# FET_Driver.net
KiCad netlist of a schematic drawn in Altium Designer
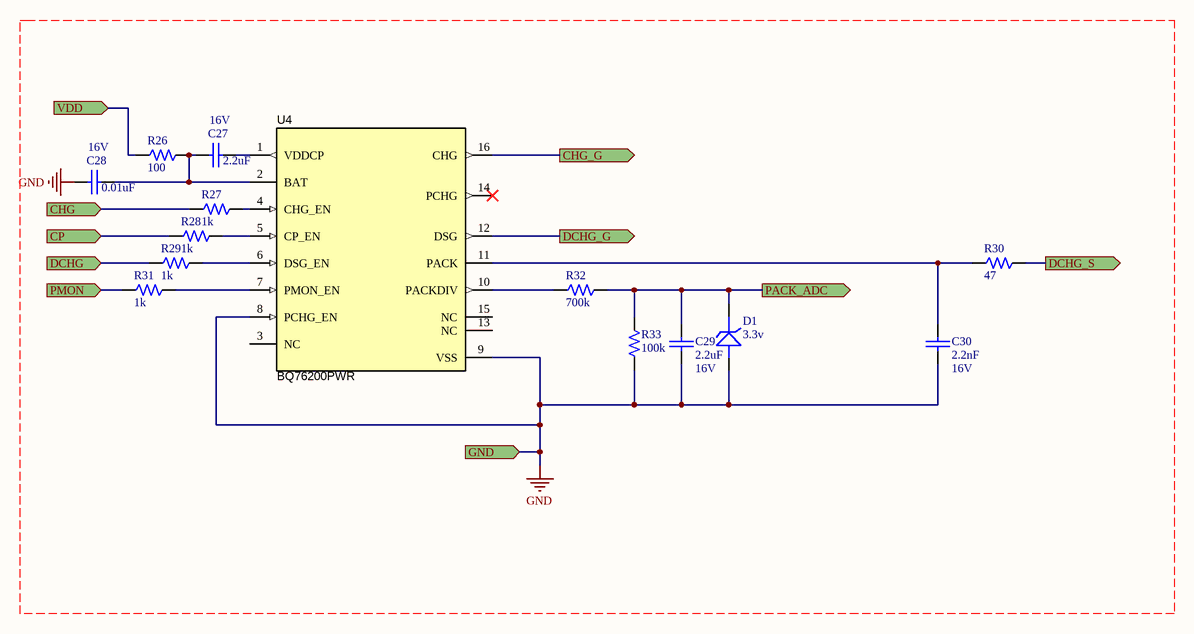
[diagram p0: FET Driver.SchDoc]

(export (version "E")
  (design (tool "Eeschema 10.0.6"))
  (components
    (comp (ref "C27")
      (value "2.2uF")
      (footprint "CAPC0603-RW")
      (description "CAP X7R .01UF 16V +-10% 0603 WALSIN L")
      (fields
        (field (name "MFG") "WALSIN")
        (field (name "TOLERANCE") "10%")
        (field (name "VOLTAGE") "16V")
        (field (name "CREATE_NAME") "Nathan")
      )
      (libsource (lib "P-Capacitors") (part "CAP0603 0.01uF 16V 10%_X7R_WALSIN"))
    )
    (comp (ref "C28")
      (value "0.01uF")
      (footprint "CAPC0603-RW")
      (description "CAP X7R .01UF 16V +-10% 0603 WALSIN L")
      (fields
        (field (name "MFG") "WALSIN")
        (field (name "TOLERANCE") "10%")
        (field (name "VOLTAGE") "16V")
        (field (name "CREATE_NAME") "Nathan")
      )
      (libsource (lib "P-Capacitors") (part "CAP0603 0.01uF 16V 10%_X7R_WALSIN"))
    )
    (comp (ref "C29")
      (value "2.2uF")
      (footprint "CAPC0603-RW")
      (description "CAP X7R .01UF 16V +-10% 0603 WALSIN L")
      (fields
        (field (name "MFG") "WALSIN")
        (field (name "TOLERANCE") "10%")
        (field (name "VOLTAGE") "16V")
        (field (name "CREATE_NAME") "Nathan")
      )
      (libsource (lib "P-Capacitors") (part "CAP0603 0.01uF 16V 10%_X7R_WALSIN"))
    )
    (comp (ref "C30")
      (value "2.2nF")
      (footprint "CAPC0603-RW")
      (description "CAP X7R .01UF 16V +-10% 0603 WALSIN L")
      (fields
        (field (name "MFG") "WALSIN")
        (field (name "TOLERANCE") "10%")
        (field (name "VOLTAGE") "16V")
        (field (name "CREATE_NAME") "Nathan")
      )
      (libsource (lib "P-Capacitors") (part "CAP0603 0.01uF 16V 10%_X7R_WALSIN"))
    )
    (comp (ref "D1")
      (value "T573004282016")
      (footprint "1206-RW")
      (description "ZD 16V 500MW 5% LL34 PAN J K")
      (fields
        (field (name "MFG") "PAN JIT")
        (field (name "POWER") "500MW")
        (field (name "MFG PART") "3.3v")
        (field (name "CREATE_NAME") "Nathan")
      )
      (libsource (lib "R-Semiconductors") (part "ZMM55-C16"))
    )
    (comp (ref "R26")
      (value "100")
      (footprint "0603-RW")
      (description "CHIP 976 OHM 100PPM +-1% 0603 WALS L")
      (fields (field (name "POWER") "0.1W") (field (name "MFG") "WALSIN") (field (name "CREATE_NAME") "Tom"))
      (libsource (lib "Q-Resistors") (part "RES0603 1/10W +-1% 976 OHM 100PPM"))
    )
    (comp (ref "R27")
      (value "1k")
      (footprint "0603-RW")
      (description "CHIP 976 OHM 100PPM +-1% 0603 WALS L")
      (fields (field (name "POWER") "0.1W") (field (name "MFG") "WALSIN") (field (name "CREATE_NAME") "Tom"))
      (libsource (lib "Q-Resistors") (part "RES0603 1/10W +-1% 976 OHM 100PPM"))
    )
    (comp (ref "R28")
      (value "1k")
      (footprint "0603-RW")
      (description "CHIP 976 OHM 100PPM +-1% 0603 WALS L")
      (fields (field (name "POWER") "0.1W") (field (name "MFG") "WALSIN") (field (name "CREATE_NAME") "Tom"))
      (libsource (lib "Q-Resistors") (part "RES0603 1/10W +-1% 976 OHM 100PPM"))
    )
    (comp (ref "R29")
      (value "1k")
      (footprint "0603-RW")
      (description "CHIP 976 OHM 100PPM +-1% 0603 WALS L")
      (fields (field (name "POWER") "0.1W") (field (name "MFG") "WALSIN") (field (name "CREATE_NAME") "Tom"))
      (libsource (lib "Q-Resistors") (part "RES0603 1/10W +-1% 976 OHM 100PPM"))
    )
    (comp (ref "R30")
      (value "47")
      (footprint "0603-RW")
      (description "CHIP 976 OHM 100PPM +-1% 0603 WALS L")
      (fields (field (name "POWER") "0.1W") (field (name "MFG") "WALSIN") (field (name "CREATE_NAME") "Tom"))
      (libsource (lib "Q-Resistors") (part "RES0603 1/10W +-1% 976 OHM 100PPM"))
    )
    (comp (ref "R31")
      (value "1k")
      (footprint "0603-RW")
      (description "CHIP 976 OHM 100PPM +-1% 0603 WALS L")
      (fields (field (name "POWER") "0.1W") (field (name "MFG") "WALSIN") (field (name "CREATE_NAME") "Tom"))
      (libsource (lib "Q-Resistors") (part "RES0603 1/10W +-1% 976 OHM 100PPM"))
    )
    (comp (ref "R32")
      (value "700k")
      (footprint "0603-RW")
      (description "CHIP 976 OHM 100PPM +-1% 0603 WALS L")
      (fields (field (name "POWER") "0.1W") (field (name "MFG") "WALSIN") (field (name "CREATE_NAME") "Tom"))
      (libsource (lib "Q-Resistors") (part "RES0603 1/10W +-1% 976 OHM 100PPM"))
    )
    (comp (ref "R33")
      (value "100k")
      (footprint "0603-RW")
      (description "CHIP 976 OHM 100PPM +-1% 0603 WALS L")
      (fields (field (name "POWER") "0.1W") (field (name "MFG") "WALSIN") (field (name "CREATE_NAME") "Tom"))
      (libsource (lib "Q-Resistors") (part "RES0603 1/10W +-1% 976 OHM 100PPM"))
    )
    (comp (ref "U4")
      (value "BQ76200PWR")
      (footprint "TSSOP16")
      (description "High-Side N-Channel FET Driver, PW0016A (TSSOP-16)")
      (fields
        (field (name "PARTNUMBER") "BQ76200PWR")
        (field (name "MANUFACTURER") "Texas Instruments")
        (field (name "ALTERNATE PARTNUMBER") "BQ76200PW")
        (field (name "PUBLISHER") "Texas Instruments")
      )
      (libsource (lib "R-Semiconductors") (part "BQ76200"))
    )
  )
  (nets
    (net (code "1") (name "/CHG") (class "Default")
      (node (ref "R27") (pin "1") (pinfunction "1_1") (pintype "passive"))
    )
    (net (code "2") (name "/CHG_G") (class "Default")
      (node (ref "U4") (pin "16") (pinfunction "CHG_16") (pintype "output"))
    )
    (net (code "3") (name "/CP") (class "Default")
      (node (ref "R28") (pin "1") (pinfunction "1_1") (pintype "passive"))
    )
    (net (code "4") (name "/DCHG") (class "Default")
      (node (ref "R29") (pin "1") (pinfunction "1_1") (pintype "passive"))
    )
    (net (code "5") (name "/DCHG_G") (class "Default")
      (node (ref "U4") (pin "12") (pinfunction "DSG_12") (pintype "output"))
    )
    (net (code "6") (name "/DCHG_S") (class "Default")
      (node (ref "R30") (pin "2") (pinfunction "2_2") (pintype "passive"))
    )
    (net (code "7") (name "/PACK_ADC") (class "Default")
      (node (ref "C29") (pin "2") (pinfunction "2_2") (pintype "passive"))
      (node (ref "D1") (pin "2") (pinfunction "K_2") (pintype "passive"))
      (node (ref "R32") (pin "2") (pinfunction "2_2") (pintype "passive"))
      (node (ref "R33") (pin "2") (pinfunction "2_2") (pintype "passive"))
    )
    (net (code "8") (name "/PMON") (class "Default")
      (node (ref "R31") (pin "1") (pinfunction "1_1") (pintype "passive"))
    )
    (net (code "9") (name "/VDD") (class "Default")
      (node (ref "R26") (pin "1") (pinfunction "1_1") (pintype "passive"))
    )
    (net (code "10") (name "GND") (class "Default")
      (node (ref "C28") (pin "1") (pinfunction "1_1") (pintype "passive"))
      (node (ref "C29") (pin "1") (pinfunction "1_1") (pintype "passive"))
      (node (ref "C30") (pin "1") (pinfunction "1_1") (pintype "passive"))
      (node (ref "D1") (pin "1") (pinfunction "A_1") (pintype "passive"))
      (node (ref "R33") (pin "1") (pinfunction "1_1") (pintype "passive"))
      (node (ref "U4") (pin "8") (pinfunction "PCHG_EN_8") (pintype "input"))
      (node (ref "U4") (pin "9") (pinfunction "VSS_9") (pintype "power_in"))
    )
    (net (code "11") (name "Net-(U4-BAT)") (class "Default")
      (node (ref "C27") (pin "1") (pinfunction "1_1") (pintype "passive"))
      (node (ref "C28") (pin "2") (pinfunction "2_2") (pintype "passive"))
      (node (ref "R26") (pin "2") (pinfunction "2_2") (pintype "passive"))
      (node (ref "U4") (pin "2") (pinfunction "BAT_2") (pintype "power_in"))
    )
    (net (code "12") (name "Net-(U4-CHG_EN)") (class "Default")
      (node (ref "R27") (pin "2") (pinfunction "2_2") (pintype "passive"))
      (node (ref "U4") (pin "4") (pinfunction "CHG_EN_4") (pintype "input"))
    )
    (net (code "13") (name "Net-(U4-CP_EN)") (class "Default")
      (node (ref "R28") (pin "2") (pinfunction "2_2") (pintype "passive"))
      (node (ref "U4") (pin "5") (pinfunction "CP_EN_5") (pintype "input"))
    )
    (net (code "14") (name "Net-(U4-DSG_EN)") (class "Default")
      (node (ref "R29") (pin "2") (pinfunction "2_2") (pintype "passive"))
      (node (ref "U4") (pin "6") (pinfunction "DSG_EN_6") (pintype "input"))
    )
    (net (code "15") (name "Net-(U4-PACK)") (class "Default")
      (node (ref "C30") (pin "2") (pinfunction "2_2") (pintype "passive"))
      (node (ref "R30") (pin "1") (pinfunction "1_1") (pintype "passive"))
      (node (ref "U4") (pin "11") (pinfunction "PACK_11") (pintype "power_in"))
    )
    (net (code "16") (name "Net-(U4-PACKDIV)") (class "Default")
      (node (ref "R32") (pin "1") (pinfunction "1_1") (pintype "passive"))
      (node (ref "U4") (pin "10") (pinfunction "PACKDIV_10") (pintype "output"))
    )
    (net (code "17") (name "Net-(U4-PMON_EN)") (class "Default")
      (node (ref "R31") (pin "2") (pinfunction "2_2") (pintype "passive"))
      (node (ref "U4") (pin "7") (pinfunction "PMON_EN_7") (pintype "input"))
    )
    (net (code "18") (name "Net-(U4-VDDCP)") (class "Default")
      (node (ref "C27") (pin "2") (pinfunction "2_2") (pintype "passive"))
      (node (ref "U4") (pin "1") (pinfunction "VDDCP_1") (pintype "output"))
    )
    (net (code "19") (name "unconnected-(U4-NC-Pad3)") (class "Default")
      (node (ref "U4") (pin "3") (pinfunction "NC_3") (pintype "passive"))
    )
    (net (code "20") (name "unconnected-(U4-NC-Pad13)") (class "Default")
      (node (ref "U4") (pin "13") (pinfunction "NC_13") (pintype "passive"))
    )
    (net (code "21") (name "unconnected-(U4-NC-Pad15)") (class "Default")
      (node (ref "U4") (pin "15") (pinfunction "NC_15") (pintype "passive"))
    )
    (net (code "22") (name "unconnected-(U4-PCHG-Pad14)") (class "Default")
      (node (ref "U4") (pin "14") (pinfunction "PCHG_14") (pintype "output+no_connect"))
    )
  )
)
